# LogicBoardFPGAEP6.net
KiCad netlist of a schematic drawn in EasyEDA Pro
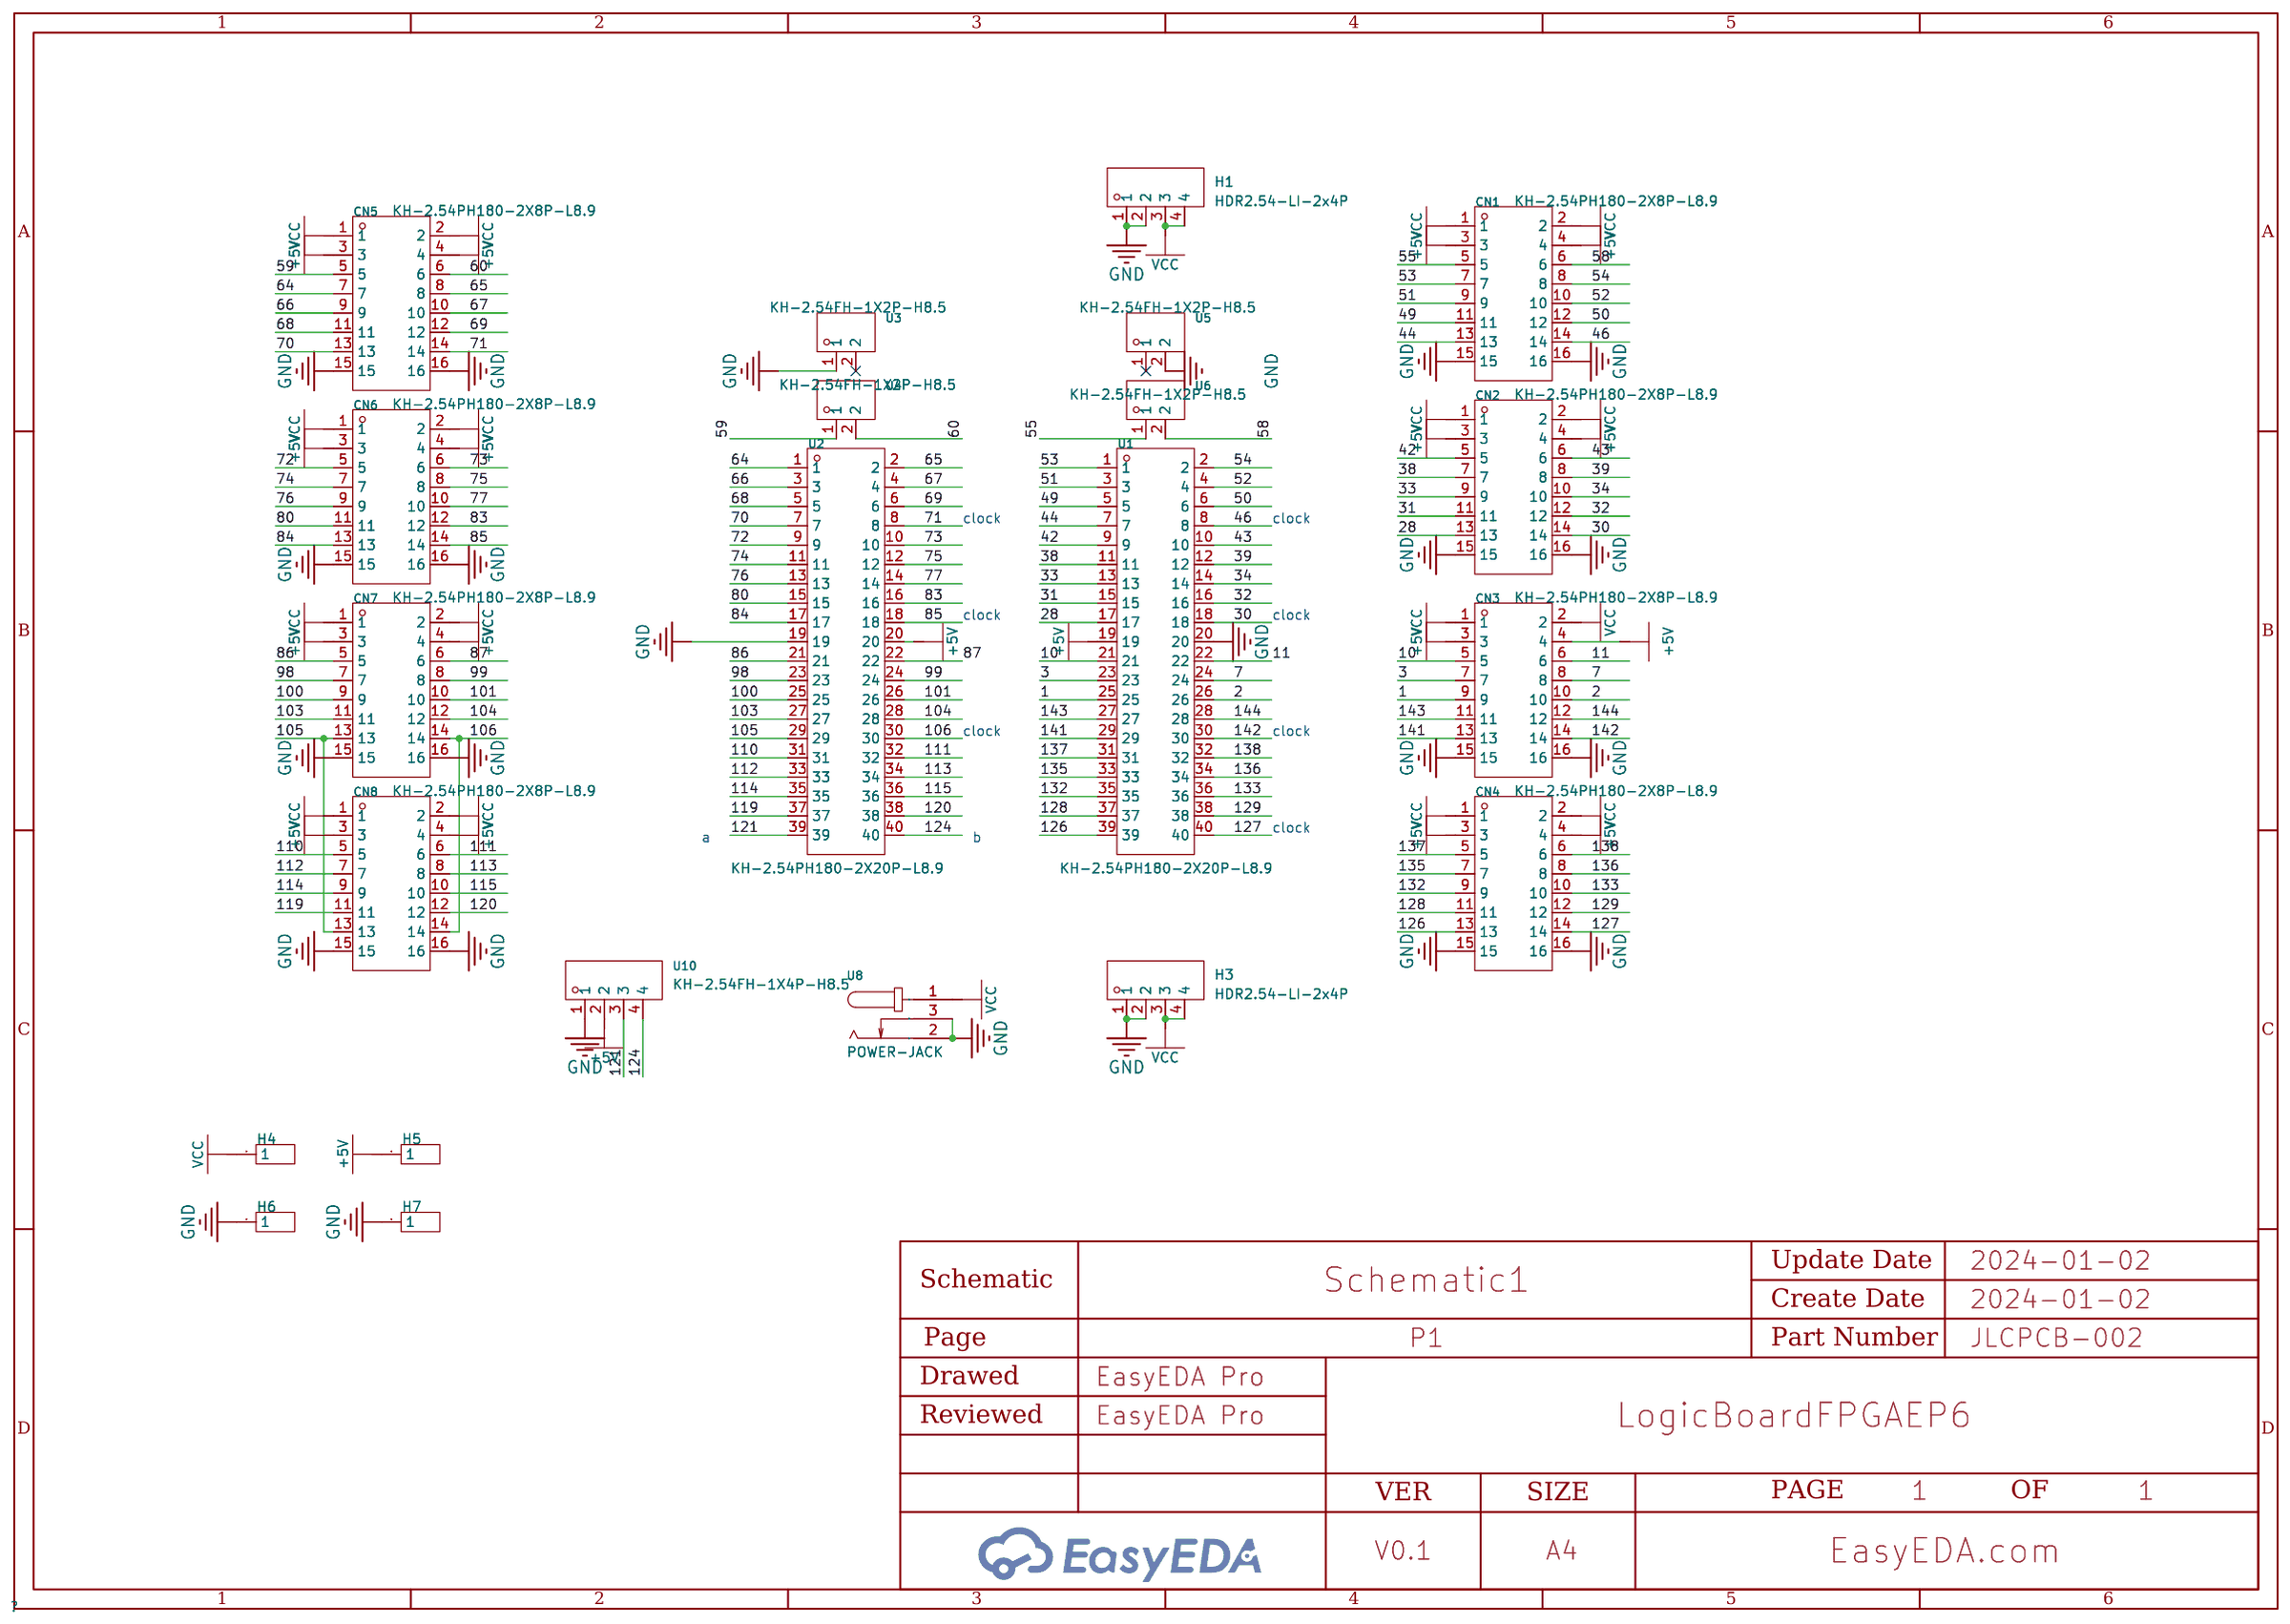
[diagram p0: schematic sheet]

(export (version "E")
  (design (tool "Eeschema 10.0.6"))
  (components
    (comp (ref "CN1")
      (value "KH-2.54PH180-2X8P-L8.9")
      (footprint "easyedapro:CONN-TH_16P-P2.54_KINGHELM_KH-2.54PH180-2X8P-L8.9")
      (fields (field (name "Manufacturer") "kinghelm(金航标)"))
      (libsource (lib "easyedapro") (part "KH-2.54PH180-2X8P-L8.9"))
    )
    (comp (ref "CN2")
      (value "KH-2.54PH180-2X8P-L8.9")
      (footprint "easyedapro:CONN-TH_16P-P2.54_KINGHELM_KH-2.54PH180-2X8P-L8.9")
      (fields (field (name "Manufacturer") "kinghelm(金航标)"))
      (libsource (lib "easyedapro") (part "KH-2.54PH180-2X8P-L8.9"))
    )
    (comp (ref "CN3")
      (value "KH-2.54PH180-2X8P-L8.9")
      (footprint "easyedapro:CONN-TH_16P-P2.54_KINGHELM_KH-2.54PH180-2X8P-L8.9")
      (fields (field (name "Manufacturer") "kinghelm(金航标)"))
      (libsource (lib "easyedapro") (part "KH-2.54PH180-2X8P-L8.9"))
    )
    (comp (ref "CN4")
      (value "KH-2.54PH180-2X8P-L8.9")
      (footprint "easyedapro:CONN-TH_16P-P2.54_KINGHELM_KH-2.54PH180-2X8P-L8.9")
      (fields (field (name "Manufacturer") "kinghelm(金航标)"))
      (libsource (lib "easyedapro") (part "KH-2.54PH180-2X8P-L8.9"))
    )
    (comp (ref "CN5")
      (value "KH-2.54PH180-2X8P-L8.9")
      (footprint "easyedapro:CONN-TH_16P-P2.54_KINGHELM_KH-2.54PH180-2X8P-L8.9")
      (fields (field (name "Manufacturer") "kinghelm(金航标)"))
      (libsource (lib "easyedapro") (part "KH-2.54PH180-2X8P-L8.9"))
    )
    (comp (ref "CN6")
      (value "KH-2.54PH180-2X8P-L8.9")
      (footprint "easyedapro:CONN-TH_16P-P2.54_KINGHELM_KH-2.54PH180-2X8P-L8.9")
      (fields (field (name "Manufacturer") "kinghelm(金航标)"))
      (libsource (lib "easyedapro") (part "KH-2.54PH180-2X8P-L8.9"))
    )
    (comp (ref "CN7")
      (value "KH-2.54PH180-2X8P-L8.9")
      (footprint "easyedapro:CONN-TH_16P-P2.54_KINGHELM_KH-2.54PH180-2X8P-L8.9")
      (fields (field (name "Manufacturer") "kinghelm(金航标)"))
      (libsource (lib "easyedapro") (part "KH-2.54PH180-2X8P-L8.9"))
    )
    (comp (ref "CN8")
      (value "KH-2.54PH180-2X8P-L8.9")
      (footprint "easyedapro:CONN-TH_16P-P2.54_KINGHELM_KH-2.54PH180-2X8P-L8.9")
      (fields (field (name "Manufacturer") "kinghelm(金航标)"))
      (libsource (lib "easyedapro") (part "KH-2.54PH180-2X8P-L8.9"))
    )
    (comp (ref "H1")
      (value "HDR2.54-LI-2x4P")
      (footprint "easyedapro:HDR-TH_4P-P2.54-V-M")
      (libsource (lib "easyedapro") (part "HDR2.54-LI-2X4P"))
    )
    (comp (ref "H3")
      (value "HDR2.54-LI-2x4P")
      (footprint "easyedapro:HDR-TH_4P-P2.54-V-M")
      (libsource (lib "easyedapro") (part "HDR2.54-LI-2X4P"))
    )
    (comp (ref "H4")
      (value "~")
      (footprint "easyedapro:HDR-TH_1P-V-M_XKB_X4611WV-01I-C28D40")
      (libsource (lib "easyedapro") (part "HDR_1x1"))
    )
    (comp (ref "H5")
      (value "~")
      (footprint "easyedapro:HDR-TH_1P-V-M_XKB_X4611WV-01I-C28D40")
      (libsource (lib "easyedapro") (part "HDR_1x1"))
    )
    (comp (ref "H6")
      (value "~")
      (footprint "easyedapro:HDR-TH_1P-V-M_XKB_X4611WV-01I-C28D40")
      (libsource (lib "easyedapro") (part "HDR_1x1"))
    )
    (comp (ref "H7")
      (value "~")
      (footprint "easyedapro:HDR-TH_1P-V-M_XKB_X4611WV-01I-C28D40")
      (libsource (lib "easyedapro") (part "HDR_1x1"))
    )
    (comp (ref "U1")
      (value "KH-2.54PH180-2X20P-L8.9")
      (footprint "easyedapro:CONN-TH_40P-P2.54_KINGHELM_KH-2.54PH180-2X20P-L8.9")
      (fields (field (name "Manufacturer") "kinghelm(金航标)"))
      (libsource (lib "easyedapro") (part "KH-2.54PH180-2X20P-L8.9"))
    )
    (comp (ref "U2")
      (value "KH-2.54PH180-2X20P-L8.9")
      (footprint "easyedapro:CONN-TH_40P-P2.54_KINGHELM_KH-2.54PH180-2X20P-L8.9")
      (fields (field (name "Manufacturer") "kinghelm(金航标)"))
      (libsource (lib "easyedapro") (part "KH-2.54PH180-2X20P-L8.9"))
    )
    (comp (ref "U3")
      (value "KH-2.54FH-1X2P-H8.5")
      (footprint "easyedapro:HDR-TH_2P-P2.54-V-F")
      (fields (field (name "Manufacturer") "kinghelm(金航标)"))
      (libsource (lib "easyedapro") (part "KH-2.54FH-1X2P-H8.5"))
    )
    (comp (ref "U4")
      (value "KH-2.54FH-1X2P-H8.5")
      (footprint "easyedapro:HDR-TH_2P-P2.54-V-F")
      (fields (field (name "Manufacturer") "kinghelm(金航标)"))
      (libsource (lib "easyedapro") (part "KH-2.54FH-1X2P-H8.5"))
    )
    (comp (ref "U5")
      (value "KH-2.54FH-1X2P-H8.5")
      (footprint "easyedapro:HDR-TH_2P-P2.54-V-F")
      (fields (field (name "Manufacturer") "kinghelm(金航标)"))
      (libsource (lib "easyedapro") (part "KH-2.54FH-1X2P-H8.5"))
    )
    (comp (ref "U6")
      (value "KH-2.54FH-1X2P-H8.5")
      (footprint "easyedapro:HDR-TH_2P-P2.54-V-F")
      (fields (field (name "Manufacturer") "kinghelm(金航标)"))
      (libsource (lib "easyedapro") (part "KH-2.54FH-1X2P-H8.5"))
    )
    (comp (ref "U8")
      (value "POWER-JACK")
      (footprint "easyedapro:DC-IN-TH_POWER-JACK")
      (libsource (lib "easyedapro") (part "POWER-JACK"))
    )
    (comp (ref "U10")
      (value "KH-2.54FH-1X4P-H8.5")
      (footprint "easyedapro:HDR-TH_4P-P2.54-V-F")
      (fields (field (name "Manufacturer") "kinghelm(金航标)"))
      (libsource (lib "easyedapro") (part "KH-2.54FH-1X4P-H8.5"))
    )
  )
  (nets
    (net (code "1") (name "+5V") (class "Default")
      (node (ref "CN1") (pin "3") (pinfunction "3_3") (pintype "input"))
      (node (ref "CN1") (pin "4") (pinfunction "4_4") (pintype "input"))
      (node (ref "CN2") (pin "3") (pinfunction "3_3") (pintype "input"))
      (node (ref "CN2") (pin "4") (pinfunction "4_4") (pintype "input"))
      (node (ref "CN3") (pin "3") (pinfunction "3_3") (pintype "input"))
      (node (ref "CN3") (pin "4") (pinfunction "4_4") (pintype "input"))
      (node (ref "CN4") (pin "3") (pinfunction "3_3") (pintype "input"))
      (node (ref "CN4") (pin "4") (pinfunction "4_4") (pintype "input"))
      (node (ref "CN5") (pin "3") (pinfunction "3_3") (pintype "input"))
      (node (ref "CN5") (pin "4") (pinfunction "4_4") (pintype "input"))
      (node (ref "CN6") (pin "3") (pinfunction "3_3") (pintype "input"))
      (node (ref "CN6") (pin "4") (pinfunction "4_4") (pintype "input"))
      (node (ref "CN7") (pin "3") (pinfunction "3_3") (pintype "input"))
      (node (ref "CN7") (pin "4") (pinfunction "4_4") (pintype "input"))
      (node (ref "CN8") (pin "3") (pinfunction "3_3") (pintype "input"))
      (node (ref "CN8") (pin "4") (pinfunction "4_4") (pintype "input"))
      (node (ref "H5") (pin "1") (pinfunction "1_1") (pintype "unspecified"))
      (node (ref "U1") (pin "19") (pinfunction "19_19") (pintype "input"))
      (node (ref "U10") (pin "2") (pinfunction "2_2") (pintype "input"))
      (node (ref "U2") (pin "20") (pinfunction "20_20") (pintype "input"))
    )
    (net (code "2") (name "/1") (class "Default")
      (node (ref "CN3") (pin "9") (pinfunction "9_9") (pintype "input"))
      (node (ref "U1") (pin "25") (pinfunction "25_25") (pintype "input"))
    )
    (net (code "3") (name "/2") (class "Default")
      (node (ref "CN3") (pin "10") (pinfunction "10_10") (pintype "input"))
      (node (ref "U1") (pin "26") (pinfunction "26_26") (pintype "input"))
    )
    (net (code "4") (name "/3") (class "Default")
      (node (ref "CN3") (pin "7") (pinfunction "7_7") (pintype "input"))
      (node (ref "U1") (pin "23") (pinfunction "23_23") (pintype "input"))
    )
    (net (code "5") (name "/7") (class "Default")
      (node (ref "CN3") (pin "8") (pinfunction "8_8") (pintype "input"))
      (node (ref "U1") (pin "24") (pinfunction "24_24") (pintype "input"))
    )
    (net (code "6") (name "/10") (class "Default")
      (node (ref "CN3") (pin "5") (pinfunction "5_5") (pintype "input"))
      (node (ref "U1") (pin "21") (pinfunction "21_21") (pintype "input"))
    )
    (net (code "7") (name "/11") (class "Default")
      (node (ref "CN3") (pin "6") (pinfunction "6_6") (pintype "input"))
      (node (ref "U1") (pin "22") (pinfunction "22_22") (pintype "input"))
    )
    (net (code "8") (name "/28") (class "Default")
      (node (ref "CN2") (pin "13") (pinfunction "13_13") (pintype "input"))
      (node (ref "U1") (pin "17") (pinfunction "17_17") (pintype "input"))
    )
    (net (code "9") (name "/30") (class "Default")
      (node (ref "CN2") (pin "14") (pinfunction "14_14") (pintype "input"))
      (node (ref "U1") (pin "18") (pinfunction "18_18") (pintype "input"))
    )
    (net (code "10") (name "/31") (class "Default")
      (node (ref "CN2") (pin "11") (pinfunction "11_11") (pintype "input"))
      (node (ref "U1") (pin "15") (pinfunction "15_15") (pintype "input"))
    )
    (net (code "11") (name "/32") (class "Default")
      (node (ref "CN2") (pin "12") (pinfunction "12_12") (pintype "input"))
      (node (ref "U1") (pin "16") (pinfunction "16_16") (pintype "input"))
    )
    (net (code "12") (name "/33") (class "Default")
      (node (ref "CN2") (pin "9") (pinfunction "9_9") (pintype "input"))
      (node (ref "U1") (pin "13") (pinfunction "13_13") (pintype "input"))
    )
    (net (code "13") (name "/34") (class "Default")
      (node (ref "CN2") (pin "10") (pinfunction "10_10") (pintype "input"))
      (node (ref "U1") (pin "14") (pinfunction "14_14") (pintype "input"))
    )
    (net (code "14") (name "/38") (class "Default")
      (node (ref "CN2") (pin "7") (pinfunction "7_7") (pintype "input"))
      (node (ref "U1") (pin "11") (pinfunction "11_11") (pintype "input"))
    )
    (net (code "15") (name "/39") (class "Default")
      (node (ref "CN2") (pin "8") (pinfunction "8_8") (pintype "input"))
      (node (ref "U1") (pin "12") (pinfunction "12_12") (pintype "input"))
    )
    (net (code "16") (name "/42") (class "Default")
      (node (ref "CN2") (pin "5") (pinfunction "5_5") (pintype "input"))
      (node (ref "U1") (pin "9") (pinfunction "9_9") (pintype "input"))
    )
    (net (code "17") (name "/43") (class "Default")
      (node (ref "CN2") (pin "6") (pinfunction "6_6") (pintype "input"))
      (node (ref "U1") (pin "10") (pinfunction "10_10") (pintype "input"))
    )
    (net (code "18") (name "/44") (class "Default")
      (node (ref "CN1") (pin "13") (pinfunction "13_13") (pintype "input"))
      (node (ref "U1") (pin "7") (pinfunction "7_7") (pintype "input"))
    )
    (net (code "19") (name "/46") (class "Default")
      (node (ref "CN1") (pin "14") (pinfunction "14_14") (pintype "input"))
      (node (ref "U1") (pin "8") (pinfunction "8_8") (pintype "input"))
    )
    (net (code "20") (name "/49") (class "Default")
      (node (ref "CN1") (pin "11") (pinfunction "11_11") (pintype "input"))
      (node (ref "U1") (pin "5") (pinfunction "5_5") (pintype "input"))
    )
    (net (code "21") (name "/50") (class "Default")
      (node (ref "CN1") (pin "12") (pinfunction "12_12") (pintype "input"))
      (node (ref "U1") (pin "6") (pinfunction "6_6") (pintype "input"))
    )
    (net (code "22") (name "/51") (class "Default")
      (node (ref "CN1") (pin "9") (pinfunction "9_9") (pintype "input"))
      (node (ref "U1") (pin "3") (pinfunction "3_3") (pintype "input"))
    )
    (net (code "23") (name "/52") (class "Default")
      (node (ref "CN1") (pin "10") (pinfunction "10_10") (pintype "input"))
      (node (ref "U1") (pin "4") (pinfunction "4_4") (pintype "input"))
    )
    (net (code "24") (name "/53") (class "Default")
      (node (ref "CN1") (pin "7") (pinfunction "7_7") (pintype "input"))
      (node (ref "U1") (pin "1") (pinfunction "1_1") (pintype "input"))
    )
    (net (code "25") (name "/54") (class "Default")
      (node (ref "CN1") (pin "8") (pinfunction "8_8") (pintype "input"))
      (node (ref "U1") (pin "2") (pinfunction "2_2") (pintype "input"))
    )
    (net (code "26") (name "/55") (class "Default")
      (node (ref "CN1") (pin "5") (pinfunction "5_5") (pintype "input"))
      (node (ref "U6") (pin "1") (pinfunction "1_1") (pintype "input"))
    )
    (net (code "27") (name "/58") (class "Default")
      (node (ref "CN1") (pin "6") (pinfunction "6_6") (pintype "input"))
      (node (ref "U6") (pin "2") (pinfunction "2_2") (pintype "input"))
    )
    (net (code "28") (name "/59") (class "Default")
      (node (ref "CN5") (pin "5") (pinfunction "5_5") (pintype "input"))
      (node (ref "U4") (pin "1") (pinfunction "1_1") (pintype "input"))
    )
    (net (code "29") (name "/60") (class "Default")
      (node (ref "CN5") (pin "6") (pinfunction "6_6") (pintype "input"))
      (node (ref "U4") (pin "2") (pinfunction "2_2") (pintype "input"))
    )
    (net (code "30") (name "/64") (class "Default")
      (node (ref "CN5") (pin "7") (pinfunction "7_7") (pintype "input"))
      (node (ref "U2") (pin "1") (pinfunction "1_1") (pintype "input"))
    )
    (net (code "31") (name "/65") (class "Default")
      (node (ref "CN5") (pin "8") (pinfunction "8_8") (pintype "input"))
      (node (ref "U2") (pin "2") (pinfunction "2_2") (pintype "input"))
    )
    (net (code "32") (name "/66") (class "Default")
      (node (ref "CN5") (pin "9") (pinfunction "9_9") (pintype "input"))
      (node (ref "U2") (pin "3") (pinfunction "3_3") (pintype "input"))
    )
    (net (code "33") (name "/67") (class "Default")
      (node (ref "CN5") (pin "10") (pinfunction "10_10") (pintype "input"))
      (node (ref "U2") (pin "4") (pinfunction "4_4") (pintype "input"))
    )
    (net (code "34") (name "/68") (class "Default")
      (node (ref "CN5") (pin "11") (pinfunction "11_11") (pintype "input"))
      (node (ref "U2") (pin "5") (pinfunction "5_5") (pintype "input"))
    )
    (net (code "35") (name "/69") (class "Default")
      (node (ref "CN5") (pin "12") (pinfunction "12_12") (pintype "input"))
      (node (ref "U2") (pin "6") (pinfunction "6_6") (pintype "input"))
    )
    (net (code "36") (name "/70") (class "Default")
      (node (ref "CN5") (pin "13") (pinfunction "13_13") (pintype "input"))
      (node (ref "U2") (pin "7") (pinfunction "7_7") (pintype "input"))
    )
    (net (code "37") (name "/71") (class "Default")
      (node (ref "CN5") (pin "14") (pinfunction "14_14") (pintype "input"))
      (node (ref "U2") (pin "8") (pinfunction "8_8") (pintype "input"))
    )
    (net (code "38") (name "/72") (class "Default")
      (node (ref "CN6") (pin "5") (pinfunction "5_5") (pintype "input"))
      (node (ref "U2") (pin "9") (pinfunction "9_9") (pintype "input"))
    )
    (net (code "39") (name "/73") (class "Default")
      (node (ref "CN6") (pin "6") (pinfunction "6_6") (pintype "input"))
      (node (ref "U2") (pin "10") (pinfunction "10_10") (pintype "input"))
    )
    (net (code "40") (name "/74") (class "Default")
      (node (ref "CN6") (pin "7") (pinfunction "7_7") (pintype "input"))
      (node (ref "U2") (pin "11") (pinfunction "11_11") (pintype "input"))
    )
    (net (code "41") (name "/75") (class "Default")
      (node (ref "CN6") (pin "8") (pinfunction "8_8") (pintype "input"))
      (node (ref "U2") (pin "12") (pinfunction "12_12") (pintype "input"))
    )
    (net (code "42") (name "/76") (class "Default")
      (node (ref "CN6") (pin "9") (pinfunction "9_9") (pintype "input"))
      (node (ref "U2") (pin "13") (pinfunction "13_13") (pintype "input"))
    )
    (net (code "43") (name "/77") (class "Default")
      (node (ref "CN6") (pin "10") (pinfunction "10_10") (pintype "input"))
      (node (ref "U2") (pin "14") (pinfunction "14_14") (pintype "input"))
    )
    (net (code "44") (name "/80") (class "Default")
      (node (ref "CN6") (pin "11") (pinfunction "11_11") (pintype "input"))
      (node (ref "U2") (pin "15") (pinfunction "15_15") (pintype "input"))
    )
    (net (code "45") (name "/83") (class "Default")
      (node (ref "CN6") (pin "12") (pinfunction "12_12") (pintype "input"))
      (node (ref "U2") (pin "16") (pinfunction "16_16") (pintype "input"))
    )
    (net (code "46") (name "/84") (class "Default")
      (node (ref "CN6") (pin "13") (pinfunction "13_13") (pintype "input"))
      (node (ref "U2") (pin "17") (pinfunction "17_17") (pintype "input"))
    )
    (net (code "47") (name "/85") (class "Default")
      (node (ref "CN6") (pin "14") (pinfunction "14_14") (pintype "input"))
      (node (ref "U2") (pin "18") (pinfunction "18_18") (pintype "input"))
    )
    (net (code "48") (name "/86") (class "Default")
      (node (ref "CN7") (pin "5") (pinfunction "5_5") (pintype "input"))
      (node (ref "U2") (pin "21") (pinfunction "21_21") (pintype "input"))
    )
    (net (code "49") (name "/87") (class "Default")
      (node (ref "CN7") (pin "6") (pinfunction "6_6") (pintype "input"))
      (node (ref "U2") (pin "22") (pinfunction "22_22") (pintype "input"))
    )
    (net (code "50") (name "/98") (class "Default")
      (node (ref "CN7") (pin "7") (pinfunction "7_7") (pintype "input"))
      (node (ref "U2") (pin "23") (pinfunction "23_23") (pintype "input"))
    )
    (net (code "51") (name "/99") (class "Default")
      (node (ref "CN7") (pin "8") (pinfunction "8_8") (pintype "input"))
      (node (ref "U2") (pin "24") (pinfunction "24_24") (pintype "input"))
    )
    (net (code "52") (name "/100") (class "Default")
      (node (ref "CN7") (pin "9") (pinfunction "9_9") (pintype "input"))
      (node (ref "U2") (pin "25") (pinfunction "25_25") (pintype "input"))
    )
    (net (code "53") (name "/101") (class "Default")
      (node (ref "CN7") (pin "10") (pinfunction "10_10") (pintype "input"))
      (node (ref "U2") (pin "26") (pinfunction "26_26") (pintype "input"))
    )
    (net (code "54") (name "/103") (class "Default")
      (node (ref "CN7") (pin "11") (pinfunction "11_11") (pintype "input"))
      (node (ref "U2") (pin "27") (pinfunction "27_27") (pintype "input"))
    )
    (net (code "55") (name "/104") (class "Default")
      (node (ref "CN7") (pin "12") (pinfunction "12_12") (pintype "input"))
      (node (ref "U2") (pin "28") (pinfunction "28_28") (pintype "input"))
    )
    (net (code "56") (name "/105") (class "Default")
      (node (ref "CN7") (pin "13") (pinfunction "13_13") (pintype "input"))
      (node (ref "CN8") (pin "13") (pinfunction "13_13") (pintype "input"))
      (node (ref "U2") (pin "29") (pinfunction "29_29") (pintype "input"))
    )
    (net (code "57") (name "/106") (class "Default")
      (node (ref "CN7") (pin "14") (pinfunction "14_14") (pintype "input"))
      (node (ref "CN8") (pin "14") (pinfunction "14_14") (pintype "input"))
      (node (ref "U2") (pin "30") (pinfunction "30_30") (pintype "input"))
    )
    (net (code "58") (name "/110") (class "Default")
      (node (ref "CN8") (pin "5") (pinfunction "5_5") (pintype "input"))
      (node (ref "U2") (pin "31") (pinfunction "31_31") (pintype "input"))
    )
    (net (code "59") (name "/111") (class "Default")
      (node (ref "CN8") (pin "6") (pinfunction "6_6") (pintype "input"))
      (node (ref "U2") (pin "32") (pinfunction "32_32") (pintype "input"))
    )
    (net (code "60") (name "/112") (class "Default")
      (node (ref "CN8") (pin "7") (pinfunction "7_7") (pintype "input"))
      (node (ref "U2") (pin "33") (pinfunction "33_33") (pintype "input"))
    )
    (net (code "61") (name "/113") (class "Default")
      (node (ref "CN8") (pin "8") (pinfunction "8_8") (pintype "input"))
      (node (ref "U2") (pin "34") (pinfunction "34_34") (pintype "input"))
    )
    (net (code "62") (name "/114") (class "Default")
      (node (ref "CN8") (pin "9") (pinfunction "9_9") (pintype "input"))
      (node (ref "U2") (pin "35") (pinfunction "35_35") (pintype "input"))
    )
    (net (code "63") (name "/115") (class "Default")
      (node (ref "CN8") (pin "10") (pinfunction "10_10") (pintype "input"))
      (node (ref "U2") (pin "36") (pinfunction "36_36") (pintype "input"))
    )
    (net (code "64") (name "/119") (class "Default")
      (node (ref "CN8") (pin "11") (pinfunction "11_11") (pintype "input"))
      (node (ref "U2") (pin "37") (pinfunction "37_37") (pintype "input"))
    )
    (net (code "65") (name "/120") (class "Default")
      (node (ref "CN8") (pin "12") (pinfunction "12_12") (pintype "input"))
      (node (ref "U2") (pin "38") (pinfunction "38_38") (pintype "input"))
    )
    (net (code "66") (name "/121") (class "Default")
      (node (ref "U10") (pin "3") (pinfunction "3_3") (pintype "input"))
      (node (ref "U2") (pin "39") (pinfunction "39_39") (pintype "input"))
    )
    (net (code "67") (name "/124") (class "Default")
      (node (ref "U10") (pin "4") (pinfunction "4_4") (pintype "input"))
      (node (ref "U2") (pin "40") (pinfunction "40_40") (pintype "input"))
    )
    (net (code "68") (name "/126") (class "Default")
      (node (ref "CN4") (pin "13") (pinfunction "13_13") (pintype "input"))
      (node (ref "U1") (pin "39") (pinfunction "39_39") (pintype "input"))
    )
    (net (code "69") (name "/127") (class "Default")
      (node (ref "CN4") (pin "14") (pinfunction "14_14") (pintype "input"))
      (node (ref "U1") (pin "40") (pinfunction "40_40") (pintype "input"))
    )
    (net (code "70") (name "/128") (class "Default")
      (node (ref "CN4") (pin "11") (pinfunction "11_11") (pintype "input"))
      (node (ref "U1") (pin "37") (pinfunction "37_37") (pintype "input"))
    )
    (net (code "71") (name "/129") (class "Default")
      (node (ref "CN4") (pin "12") (pinfunction "12_12") (pintype "input"))
      (node (ref "U1") (pin "38") (pinfunction "38_38") (pintype "input"))
    )
    (net (code "72") (name "/132") (class "Default")
      (node (ref "CN4") (pin "9") (pinfunction "9_9") (pintype "input"))
      (node (ref "U1") (pin "35") (pinfunction "35_35") (pintype "input"))
    )
    (net (code "73") (name "/133") (class "Default")
      (node (ref "CN4") (pin "10") (pinfunction "10_10") (pintype "input"))
      (node (ref "U1") (pin "36") (pinfunction "36_36") (pintype "input"))
    )
    (net (code "74") (name "/135") (class "Default")
      (node (ref "CN4") (pin "7") (pinfunction "7_7") (pintype "input"))
      (node (ref "U1") (pin "33") (pinfunction "33_33") (pintype "input"))
    )
    (net (code "75") (name "/136") (class "Default")
      (node (ref "CN4") (pin "8") (pinfunction "8_8") (pintype "input"))
      (node (ref "U1") (pin "34") (pinfunction "34_34") (pintype "input"))
    )
    (net (code "76") (name "/137") (class "Default")
      (node (ref "CN4") (pin "5") (pinfunction "5_5") (pintype "input"))
      (node (ref "U1") (pin "31") (pinfunction "31_31") (pintype "input"))
    )
    (net (code "77") (name "/138") (class "Default")
      (node (ref "CN4") (pin "6") (pinfunction "6_6") (pintype "input"))
      (node (ref "U1") (pin "32") (pinfunction "32_32") (pintype "input"))
    )
    (net (code "78") (name "/141") (class "Default")
      (node (ref "CN3") (pin "13") (pinfunction "13_13") (pintype "input"))
      (node (ref "U1") (pin "29") (pinfunction "29_29") (pintype "input"))
    )
    (net (code "79") (name "/142") (class "Default")
      (node (ref "CN3") (pin "14") (pinfunction "14_14") (pintype "input"))
      (node (ref "U1") (pin "30") (pinfunction "30_30") (pintype "input"))
    )
    (net (code "80") (name "/143") (class "Default")
      (node (ref "CN3") (pin "11") (pinfunction "11_11") (pintype "input"))
      (node (ref "U1") (pin "27") (pinfunction "27_27") (pintype "input"))
    )
    (net (code "81") (name "/144") (class "Default")
      (node (ref "CN3") (pin "12") (pinfunction "12_12") (pintype "input"))
      (node (ref "U1") (pin "28") (pinfunction "28_28") (pintype "input"))
    )
    (net (code "82") (name "GND") (class "Default")
      (node (ref "CN1") (pin "15") (pinfunction "15_15") (pintype "input"))
      (node (ref "CN1") (pin "16") (pinfunction "16_16") (pintype "input"))
      (node (ref "CN2") (pin "15") (pinfunction "15_15") (pintype "input"))
      (node (ref "CN2") (pin "16") (pinfunction "16_16") (pintype "input"))
      (node (ref "CN3") (pin "15") (pinfunction "15_15") (pintype "input"))
      (node (ref "CN3") (pin "16") (pinfunction "16_16") (pintype "input"))
      (node (ref "CN4") (pin "15") (pinfunction "15_15") (pintype "input"))
      (node (ref "CN4") (pin "16") (pinfunction "16_16") (pintype "input"))
      (node (ref "CN5") (pin "15") (pinfunction "15_15") (pintype "input"))
      (node (ref "CN5") (pin "16") (pinfunction "16_16") (pintype "input"))
      (node (ref "CN6") (pin "15") (pinfunction "15_15") (pintype "input"))
      (node (ref "CN6") (pin "16") (pinfunction "16_16") (pintype "input"))
      (node (ref "CN7") (pin "15") (pinfunction "15_15") (pintype "input"))
      (node (ref "CN7") (pin "16") (pinfunction "16_16") (pintype "input"))
      (node (ref "CN8") (pin "15") (pinfunction "15_15") (pintype "input"))
      (node (ref "CN8") (pin "16") (pinfunction "16_16") (pintype "input"))
      (node (ref "H1") (pin "1") (pinfunction "1_1") (pintype "input"))
      (node (ref "H1") (pin "2") (pinfunction "2_2") (pintype "input"))
      (node (ref "H3") (pin "1") (pinfunction "1_1") (pintype "input"))
      (node (ref "H3") (pin "2") (pinfunction "2_2") (pintype "input"))
      (node (ref "H6") (pin "1") (pinfunction "1_1") (pintype "unspecified"))
      (node (ref "H7") (pin "1") (pinfunction "1_1") (pintype "unspecified"))
      (node (ref "U1") (pin "20") (pinfunction "20_20") (pintype "input"))
      (node (ref "U10") (pin "1") (pinfunction "1_1") (pintype "input"))
      (node (ref "U2") (pin "19") (pinfunction "19_19") (pintype "input"))
      (node (ref "U3") (pin "1") (pinfunction "1_1") (pintype "input"))
      (node (ref "U5") (pin "2") (pinfunction "2_2") (pintype "input"))
      (node (ref "U8") (pin "2") (pinfunction "2_2") (pintype "input"))
      (node (ref "U8") (pin "3") (pinfunction "3_3") (pintype "input"))
    )
    (net (code "83") (name "VCC") (class "Default")
      (node (ref "CN1") (pin "1") (pinfunction "1_1") (pintype "input"))
      (node (ref "CN1") (pin "2") (pinfunction "2_2") (pintype "input"))
      (node (ref "CN2") (pin "1") (pinfunction "1_1") (pintype "input"))
      (node (ref "CN2") (pin "2") (pinfunction "2_2") (pintype "input"))
      (node (ref "CN3") (pin "1") (pinfunction "1_1") (pintype "input"))
      (node (ref "CN3") (pin "2") (pinfunction "2_2") (pintype "input"))
      (node (ref "CN4") (pin "1") (pinfunction "1_1") (pintype "input"))
      (node (ref "CN4") (pin "2") (pinfunction "2_2") (pintype "input"))
      (node (ref "CN5") (pin "1") (pinfunction "1_1") (pintype "input"))
      (node (ref "CN5") (pin "2") (pinfunction "2_2") (pintype "input"))
      (node (ref "CN6") (pin "1") (pinfunction "1_1") (pintype "input"))
      (node (ref "CN6") (pin "2") (pinfunction "2_2") (pintype "input"))
      (node (ref "CN7") (pin "1") (pinfunction "1_1") (pintype "input"))
      (node (ref "CN7") (pin "2") (pinfunction "2_2") (pintype "input"))
      (node (ref "CN8") (pin "1") (pinfunction "1_1") (pintype "input"))
      (node (ref "CN8") (pin "2") (pinfunction "2_2") (pintype "input"))
      (node (ref "H1") (pin "3") (pinfunction "3_3") (pintype "input"))
      (node (ref "H1") (pin "4") (pinfunction "4_4") (pintype "input"))
      (node (ref "H3") (pin "3") (pinfunction "3_3") (pintype "input"))
      (node (ref "H3") (pin "4") (pinfunction "4_4") (pintype "input"))
      (node (ref "H4") (pin "1") (pinfunction "1_1") (pintype "unspecified"))
      (node (ref "U8") (pin "1") (pinfunction "1_1") (pintype "input"))
    )
    (net (code "84") (name "unconnected-(U3-Pad2)") (class "Default")
      (node (ref "U3") (pin "2") (pinfunction "2_2") (pintype "input+no_connect"))
    )
    (net (code "85") (name "unconnected-(U5-Pad1)") (class "Default")
      (node (ref "U5") (pin "1") (pinfunction "1_1") (pintype "input+no_connect"))
    )
  )
)
